# Serial_Expansion.net
KiCad netlist of a schematic drawn in Altium Designer
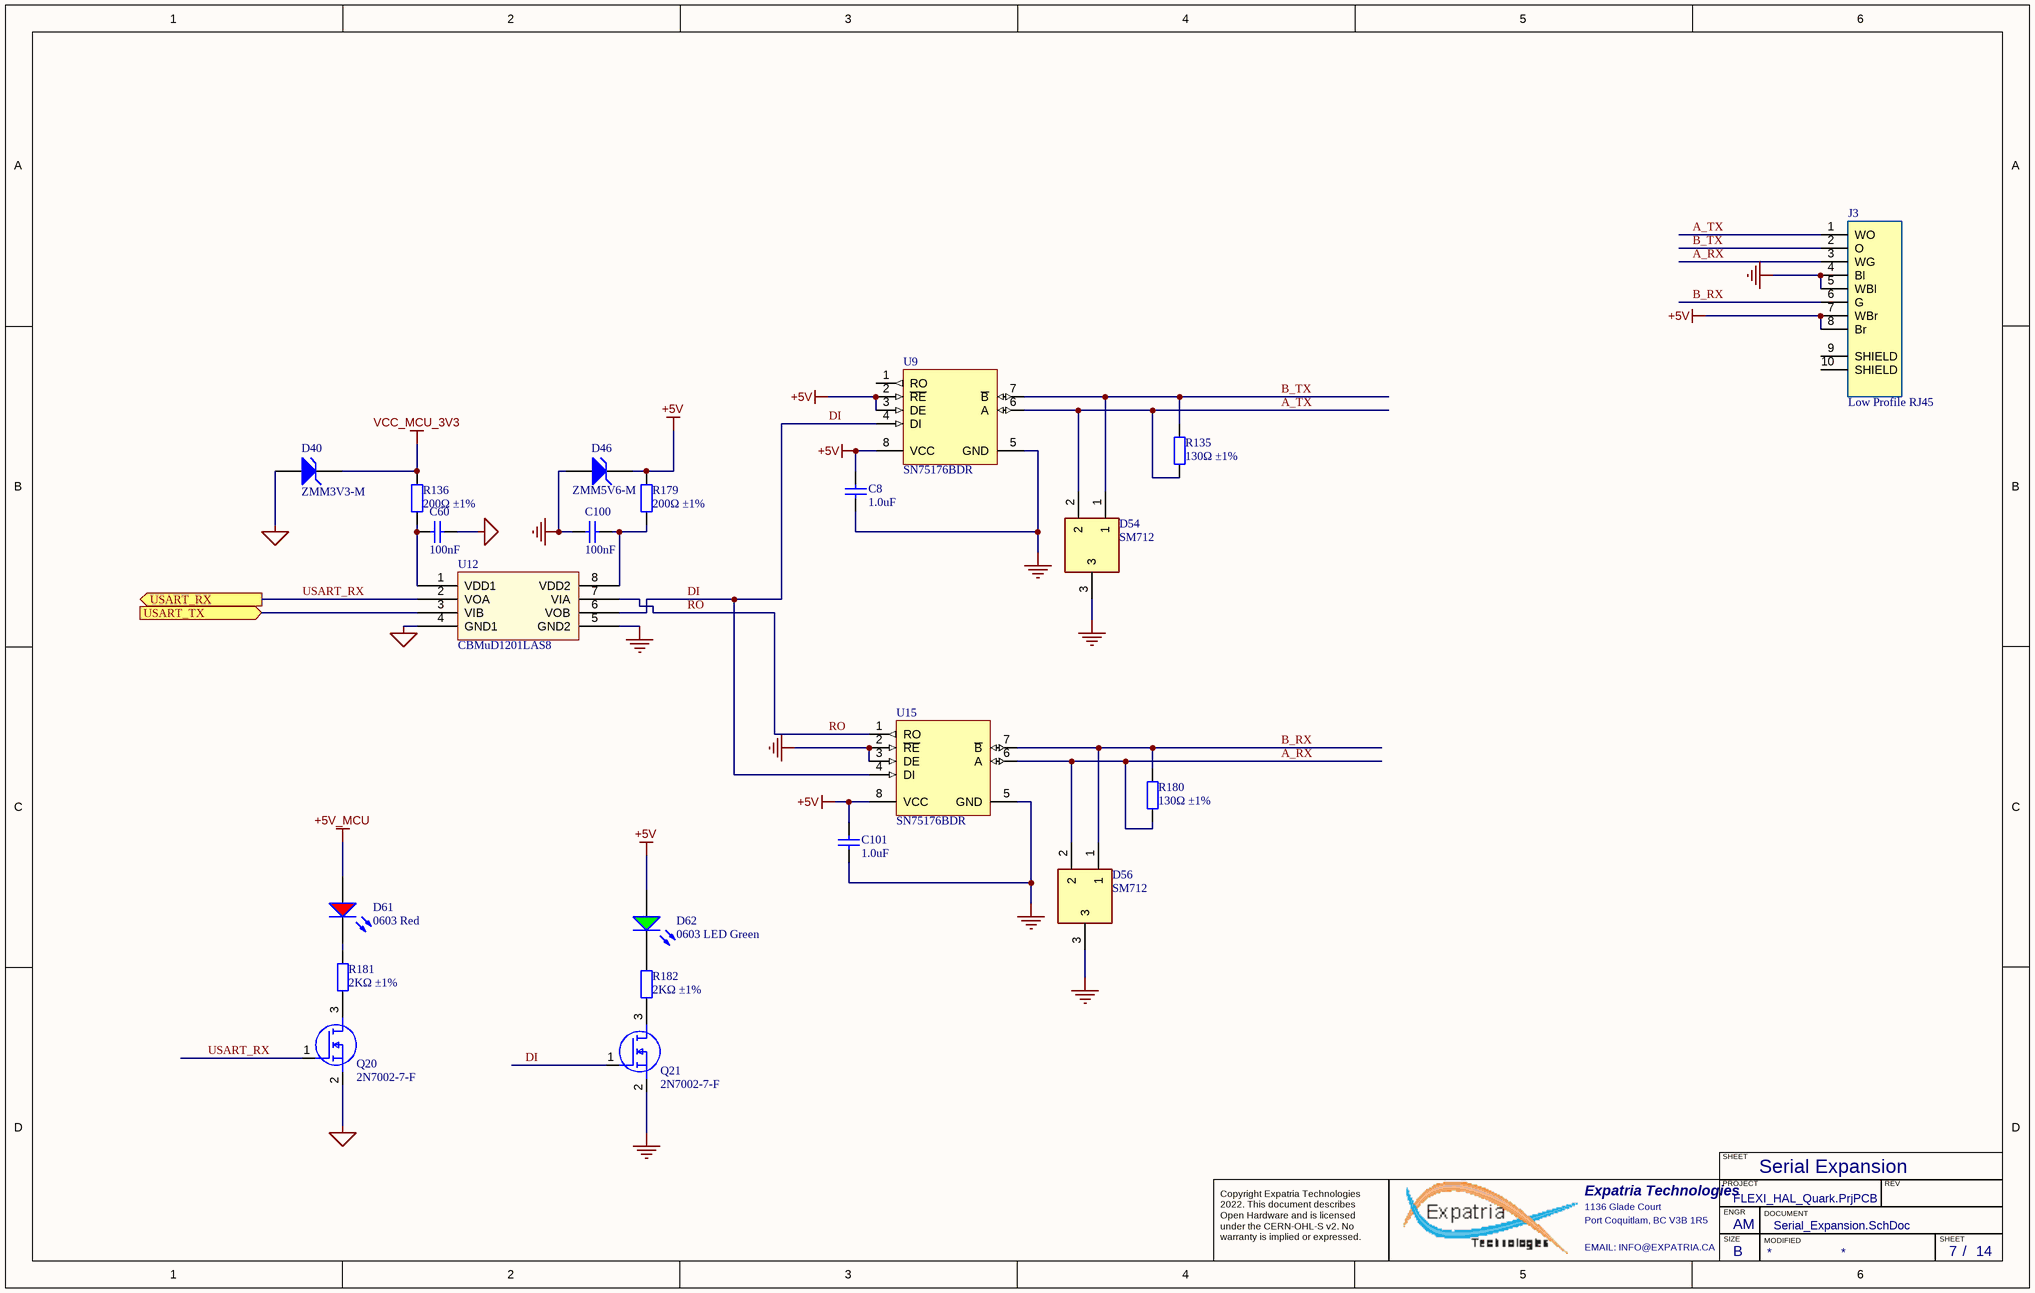
[diagram p0: Serial_Expansion.SchDoc]

(export (version "E")
  (design (tool "Eeschema 10.0.6"))
  (components
    (comp (ref "C8")
      (value "1.0uF")
      (footprint "0402_C")
      (description "Chip capacitor")
      (fields
        (field (name "MANUFACTURER") "Samsung Electro-Mechanics")
        (field (name "PARTNUMBER") "CL05A105KA5NQNC")
      )
      (libsource (lib "Cap") (part "0402 1.0uF (105) 10% 25V"))
    )
    (comp (ref "C60")
      (value "100nF")
      (footprint "0402_C")
      (description "16V 100nF X7R ±10% 0402 Multilayer Ceramic Capacitors MLCC - SMD/SMT ROHS")
      (fields (field (name "MANUFACTURER") "Samsung Electro-Mechanics") (field (name "TOLERANCE") "10%"))
      (libsource (lib "Sienci_Labs") (part "0402 100nF (104) 10% 16V"))
    )
    (comp (ref "C100")
      (value "100nF")
      (footprint "0402_C")
      (description "16V 100nF X7R ±10% 0402 Multilayer Ceramic Capacitors MLCC - SMD/SMT ROHS")
      (fields (field (name "MANUFACTURER") "Samsung Electro-Mechanics") (field (name "TOLERANCE") "10%"))
      (libsource (lib "Sienci_Labs") (part "0402 100nF (104) 10% 16V"))
    )
    (comp (ref "C101")
      (value "1.0uF")
      (footprint "0402_C")
      (description "Chip capacitor")
      (fields
        (field (name "MANUFACTURER") "Samsung Electro-Mechanics")
        (field (name "PARTNUMBER") "CL05A105KA5NQNC")
      )
      (libsource (lib "Cap") (part "0402 1.0uF (105) 10% 25V"))
    )
    (comp (ref "D40")
      (value "ZMM3V3-M")
      (footprint "LL-34")
      (description "Single 3.1V~3.5V 500mW 3.3V LL-34 Zener Diodes ROHS")
      (fields (field (name "MANUFACTURER") "ST(Semtech)"))
      (libsource (lib "Sienci_Labs") (part "LL-34 ZMM3V3-M"))
    )
    (comp (ref "D46")
      (value "ZMM5V6-M")
      (footprint "LL-34")
      (description "Single 5.2V~6V 500mW 5.6V LL-34 Zener Diodes ROHS")
      (fields (field (name "MANUFACTURER") "ST(Semtech)"))
      (libsource (lib "Sienci_Labs") (part "LL-34 ZMM5V6-M"))
    )
    (comp (ref "D54")
      (value "SM712")
      (footprint "SamacSys:SOT95P230X117-3N")
      (description "Bidirectional 12V (Max), 7V (Max) 7.5V / 13.3V 10V / 20V 12A(8/20us) SOT-23-3 TVS RoHS")
      (libsource (lib "*") (part "CDSOT23-SM712"))
    )
    (comp (ref "D56")
      (value "SM712")
      (footprint "SamacSys:SOT95P230X117-3N")
      (description "Bidirectional 12V (Max), 7V (Max) 7.5V / 13.3V 10V / 20V 12A(8/20us) SOT-23-3 TVS RoHS")
      (libsource (lib "*") (part "CDSOT23-SM712"))
    )
    (comp (ref "D61")
      (value "0603 Red")
      (footprint "0603_LED_S1")
      (fields
        (field (name "MANUFACTURER") "Everlight Elec")
        (field (name "MANUFACTURER PART NUMBER") "19-213SURC/S530-A3/TR8")
      )
      (libsource (lib "Sienci_Labs") (part "19-213SURC/S530-A3/TR8"))
    )
    (comp (ref "D62")
      (value "0603 LED Green")
      (footprint "0603_LED_S1")
      (fields
        (field (name "MANUFACTURER PART NUMBER") "19-217/GHC-YR1S2/3T")
        (field (name "MANUFACTURER") "Everlight Elec")
      )
      (libsource (lib "Sienci_Labs") (part "19-217/GHC-YR1S2/3T"))
    )
    (comp (ref "J3")
      (value "Low Profile RJ45")
      (footprint "RJ45-SMD_MJ88-B011-HLSV6-P")
      (description "Micro USB")
      (fields (field (name "MF") "Heling"))
      (libsource (lib "Universal_CNC_Breakout") (part "MJ88-B011-HLSV6-P"))
    )
    (comp (ref "Q20")
      (value "2N7002-7-F")
      (footprint "SOT-23(SOT-23-3)")
      (description "60V 115mA 7.5Ω@5V,50mA 370mW N Channel SOT-23 MOSFETs ROHS")
      (fields (field (name "MANUFACTURER") "Diodes Inc.") (field (name "MOUSER PART NUMBER") "621-2N7002-F"))
      (libsource (lib "Sienci_Labs") (part "2N7002-7-F"))
    )
    (comp (ref "Q21")
      (value "2N7002-7-F")
      (footprint "SOT-23(SOT-23-3)")
      (description "60V 115mA 7.5Ω@5V,50mA 370mW N Channel SOT-23 MOSFETs ROHS")
      (fields (field (name "MANUFACTURER") "Diodes Inc.") (field (name "MOUSER PART NUMBER") "621-2N7002-F"))
      (libsource (lib "Sienci_Labs") (part "2N7002-7-F"))
    )
    (comp (ref "R135")
      (value "130Ω ±1%")
      (footprint "0603_R")
      (description "Chip resistor")
      (fields (field (name "MANUFACTURER") "Uniroyal Elec") (field (name "PARTNUMBER") "0603WAF1300T5E"))
      (libsource (lib "RES") (part "0603 130R (1300) 1%"))
    )
    (comp (ref "R136")
      (value "200Ω ±1%")
      (footprint "0402_R")
      (description "Chip resistor")
      (fields
        (field (name "MANUFACTURER") "Uniroyal Elec")
        (field (name "MANUFACTURER PART NUMBER") "0402WGF2000TCE")
      )
      (libsource (lib "RES") (part "0402 200R (2000) 1%"))
    )
    (comp (ref "R179")
      (value "200Ω ±1%")
      (footprint "0402_R")
      (description "Chip resistor")
      (fields
        (field (name "MANUFACTURER") "Uniroyal Elec")
        (field (name "MANUFACTURER PART NUMBER") "0402WGF2000TCE")
      )
      (libsource (lib "RES") (part "0402 200R (2000) 1%"))
    )
    (comp (ref "R180")
      (value "130Ω ±1%")
      (footprint "0603_R")
      (description "Chip resistor")
      (fields (field (name "MANUFACTURER") "Uniroyal Elec") (field (name "PARTNUMBER") "0603WAF1300T5E"))
      (libsource (lib "RES") (part "0603 130R (1300) 1%"))
    )
    (comp (ref "R181")
      (value "2KΩ ±1%")
      (footprint "0402_R")
      (description "Chip resistor")
      (fields
        (field (name "MANUFACTURER") "Uniroyal Elec")
        (field (name "MANUFACTURER PART NUMBER") "0402WGF2001TCE")
      )
      (libsource (lib "RES") (part "0402 2K (2001) 1%"))
    )
    (comp (ref "R182")
      (value "2KΩ ±1%")
      (footprint "0402_R")
      (description "Chip resistor")
      (fields
        (field (name "MANUFACTURER") "Uniroyal Elec")
        (field (name "MANUFACTURER PART NUMBER") "0402WGF2001TCE")
      )
      (libsource (lib "RES") (part "0402 2K (2001) 1%"))
    )
    (comp (ref "U9")
      (value "SN75176BDR")
      (footprint "Miscellaneous Devices LC:SOIC-8_150mil")
      (description "RS-485/RS-422")
      (libsource (lib "IC") (part "SN75176BDR_[C7063]"))
    )
    (comp (ref "U12")
      (value "CBMuD1201LAS8")
      (footprint "SOIC-8_150mil")
      (description "Dual Channel Isolator")
      (fields (field (name "MANUFACTURER") "Corebai Microelectronics"))
      (libsource (lib "Sienci_Labs") (part "CBMuD1201LAS8"))
    )
    (comp (ref "U15")
      (value "SN75176BDR")
      (footprint "Miscellaneous Devices LC:SOIC-8_150mil")
      (description "RS-485/RS-422")
      (libsource (lib "IC") (part "SN75176BDR_[C7063]"))
    )
  )
  (nets
    (net (code "1") (name "+5V") (class "Default")
      (node (ref "C101") (pin "2") (pinfunction "2_2") (pintype "passive"))
      (node (ref "C8") (pin "2") (pinfunction "2_2") (pintype "passive"))
      (node (ref "D46") (pin "2") (pinfunction "K_2") (pintype "passive"))
      (node (ref "D62") (pin "A") (pinfunction "A_A") (pintype "passive"))
      (node (ref "J3") (pin "7") (pinfunction "WBr_7") (pintype "passive"))
      (node (ref "J3") (pin "8") (pinfunction "Br_8") (pintype "passive"))
      (node (ref "R179") (pin "2") (pinfunction "2_2") (pintype "passive"))
      (node (ref "U15") (pin "8") (pinfunction "VCC_8") (pintype "power_in"))
      (node (ref "U9") (pin "2") (pinfunction "~{RE}_2") (pintype "input"))
      (node (ref "U9") (pin "3") (pinfunction "DE_3") (pintype "input"))
      (node (ref "U9") (pin "8") (pinfunction "VCC_8") (pintype "power_in"))
    )
    (net (code "2") (name "+5V_MCU") (class "Default")
      (node (ref "D61") (pin "A") (pinfunction "A_A") (pintype "passive"))
    )
    (net (code "3") (name "/A_RX") (class "Default")
      (node (ref "D56") (pin "2") (pinfunction "2_2") (pintype "passive"))
      (node (ref "J3") (pin "3") (pinfunction "WG_3") (pintype "passive"))
      (node (ref "R180") (pin "1") (pinfunction "1_1") (pintype "passive"))
      (node (ref "U15") (pin "6") (pinfunction "A_6") (pintype "bidirectional"))
    )
    (net (code "4") (name "/A_TX") (class "Default")
      (node (ref "D54") (pin "2") (pinfunction "2_2") (pintype "passive"))
      (node (ref "J3") (pin "1") (pinfunction "WO_1") (pintype "power_in"))
      (node (ref "R135") (pin "1") (pinfunction "1_1") (pintype "passive"))
      (node (ref "U9") (pin "6") (pinfunction "A_6") (pintype "bidirectional"))
    )
    (net (code "5") (name "/B_RX") (class "Default")
      (node (ref "D56") (pin "1") (pinfunction "1_1") (pintype "passive"))
      (node (ref "J3") (pin "6") (pinfunction "G_6") (pintype "passive"))
      (node (ref "R180") (pin "2") (pinfunction "2_2") (pintype "passive"))
      (node (ref "U15") (pin "7") (pinfunction "~{B}_7") (pintype "bidirectional"))
    )
    (net (code "6") (name "/B_TX") (class "Default")
      (node (ref "D54") (pin "1") (pinfunction "1_1") (pintype "passive"))
      (node (ref "J3") (pin "2") (pinfunction "O_2") (pintype "passive"))
      (node (ref "R135") (pin "2") (pinfunction "2_2") (pintype "passive"))
      (node (ref "U9") (pin "7") (pinfunction "~{B}_7") (pintype "bidirectional"))
    )
    (net (code "7") (name "/DI") (class "Default")
      (node (ref "Q21") (pin "1") (pinfunction "G_1") (pintype "passive"))
      (node (ref "U12") (pin "6") (pinfunction "VOB_6") (pintype "passive"))
      (node (ref "U15") (pin "4") (pinfunction "DI_4") (pintype "input"))
      (node (ref "U9") (pin "4") (pinfunction "DI_4") (pintype "input"))
    )
    (net (code "8") (name "/RO") (class "Default")
      (node (ref "U12") (pin "7") (pinfunction "VIA_7") (pintype "passive"))
      (node (ref "U15") (pin "1") (pinfunction "RO_1") (pintype "output"))
    )
    (net (code "9") (name "/USART_RX") (class "Default")
      (node (ref "Q20") (pin "1") (pinfunction "G_1") (pintype "passive"))
      (node (ref "U12") (pin "2") (pinfunction "VOA_2") (pintype "passive"))
    )
    (net (code "10") (name "/USART_TX") (class "Default")
      (node (ref "U12") (pin "3") (pinfunction "VIB_3") (pintype "passive"))
    )
    (net (code "11") (name "GND") (class "Default")
      (node (ref "C100") (pin "1") (pinfunction "1_1") (pintype "passive"))
      (node (ref "C101") (pin "1") (pinfunction "1_1") (pintype "passive"))
      (node (ref "C8") (pin "1") (pinfunction "1_1") (pintype "passive"))
      (node (ref "D46") (pin "1") (pinfunction "A_1") (pintype "passive"))
      (node (ref "D54") (pin "3") (pinfunction "3_3") (pintype "passive"))
      (node (ref "D56") (pin "3") (pinfunction "3_3") (pintype "passive"))
      (node (ref "J3") (pin "4") (pinfunction "Bl_4") (pintype "passive"))
      (node (ref "J3") (pin "5") (pinfunction "WBl_5") (pintype "power_in"))
      (node (ref "Q21") (pin "2") (pinfunction "S_2") (pintype "passive"))
      (node (ref "U12") (pin "5") (pinfunction "GND2_5") (pintype "passive"))
      (node (ref "U15") (pin "2") (pinfunction "~{RE}_2") (pintype "input"))
      (node (ref "U15") (pin "3") (pinfunction "DE_3") (pintype "input"))
      (node (ref "U15") (pin "5") (pinfunction "GND_5") (pintype "power_in"))
      (node (ref "U9") (pin "5") (pinfunction "GND_5") (pintype "power_in"))
    )
    (net (code "12") (name "MCU_GND") (class "Default")
      (node (ref "C60") (pin "2") (pinfunction "2_2") (pintype "passive"))
      (node (ref "D40") (pin "1") (pinfunction "A_1") (pintype "passive"))
      (node (ref "Q20") (pin "2") (pinfunction "S_2") (pintype "passive"))
      (node (ref "U12") (pin "4") (pinfunction "GND1_4") (pintype "passive"))
    )
    (net (code "13") (name "Net-(D61-PadK)") (class "Default")
      (node (ref "D61") (pin "K") (pinfunction "K_K") (pintype "passive"))
      (node (ref "R181") (pin "2") (pinfunction "2_2") (pintype "passive"))
    )
    (net (code "14") (name "Net-(D62-PadK)") (class "Default")
      (node (ref "D62") (pin "K") (pinfunction "K_K") (pintype "passive"))
      (node (ref "R182") (pin "2") (pinfunction "2_2") (pintype "passive"))
    )
    (net (code "15") (name "Net-(Q20-D)") (class "Default")
      (node (ref "Q20") (pin "3") (pinfunction "D_3") (pintype "passive"))
      (node (ref "R181") (pin "1") (pinfunction "1_1") (pintype "passive"))
    )
    (net (code "16") (name "Net-(Q21-D)") (class "Default")
      (node (ref "Q21") (pin "3") (pinfunction "D_3") (pintype "passive"))
      (node (ref "R182") (pin "1") (pinfunction "1_1") (pintype "passive"))
    )
    (net (code "17") (name "Net-(U12-VDD1)") (class "Default")
      (node (ref "C60") (pin "1") (pinfunction "1_1") (pintype "passive"))
      (node (ref "R136") (pin "1") (pinfunction "1_1") (pintype "passive"))
      (node (ref "U12") (pin "1") (pinfunction "VDD1_1") (pintype "passive"))
    )
    (net (code "18") (name "Net-(U12-VDD2)") (class "Default")
      (node (ref "C100") (pin "2") (pinfunction "2_2") (pintype "passive"))
      (node (ref "R179") (pin "1") (pinfunction "1_1") (pintype "passive"))
      (node (ref "U12") (pin "8") (pinfunction "VDD2_8") (pintype "passive"))
    )
    (net (code "19") (name "VCC_MCU_3V3") (class "Default")
      (node (ref "D40") (pin "2") (pinfunction "K_2") (pintype "passive"))
      (node (ref "R136") (pin "2") (pinfunction "2_2") (pintype "passive"))
    )
    (net (code "20") (name "unconnected-(J3-SHIELD-Pad9)") (class "Default")
      (node (ref "J3") (pin "9") (pinfunction "SHIELD_9") (pintype "passive"))
    )
    (net (code "21") (name "unconnected-(J3-SHIELD-Pad10)") (class "Default")
      (node (ref "J3") (pin "10") (pinfunction "SHIELD_10") (pintype "passive"))
    )
    (net (code "22") (name "unconnected-(U9-RO-Pad1)") (class "Default")
      (node (ref "U9") (pin "1") (pinfunction "RO_1") (pintype "output"))
    )
  )
)
